# PCIE.net
KiCad netlist of a schematic drawn in Altium Designer
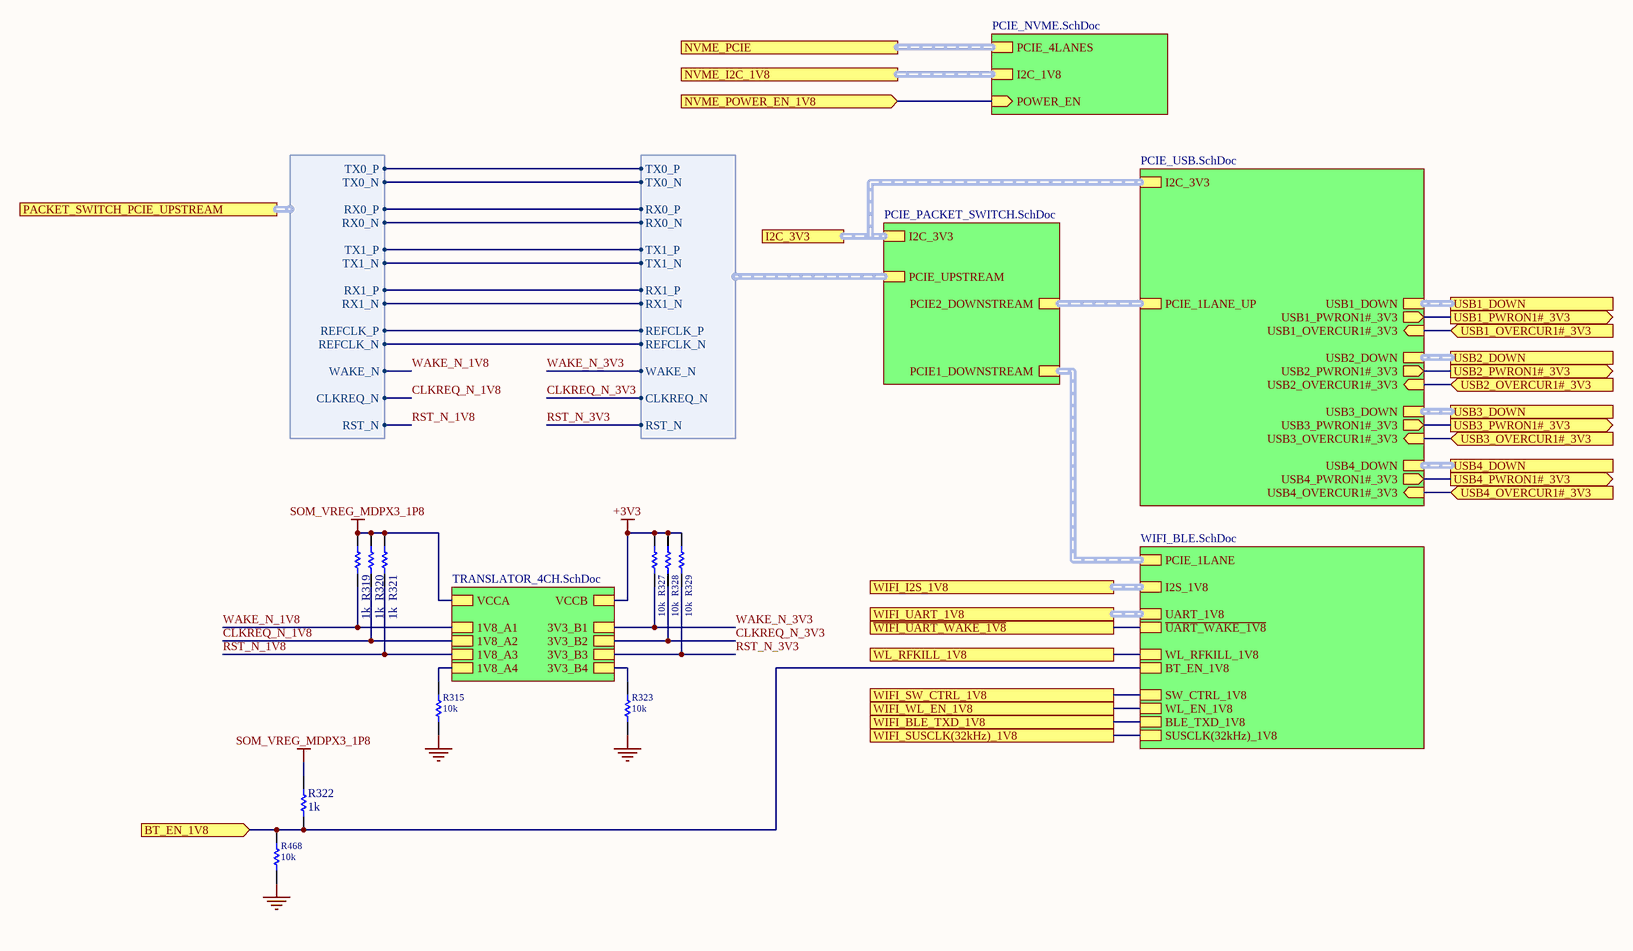
[diagram p0: PCIE.SchDoc]

(export (version "E")
  (design (tool "Eeschema 10.0.6"))
  (components
    (comp (ref "R315")
      (value "10k")
      (footprint "RES-0201")
      (description "RES CHIP 0201 10k 1% 1/20W")
      (fields (field (name "POWER") "50mW") (field (name "TOLERANCE") "1%"))
      (libsource (lib "Clean") (part "RES"))
    )
    (comp (ref "R319")
      (value "1k")
      (footprint "RES-0201")
      (description "RES CHIP 0201 1k 1% 1/20W")
      (fields (field (name "POWER") "50mW") (field (name "TOLERANCE") "1%"))
      (libsource (lib "Clean") (part "RES"))
    )
    (comp (ref "R320")
      (value "1k")
      (footprint "RES-0201")
      (description "RES CHIP 0201 1k 1% 1/20W")
      (fields (field (name "POWER") "50mW") (field (name "TOLERANCE") "1%"))
      (libsource (lib "Clean") (part "RES"))
    )
    (comp (ref "R321")
      (value "1k")
      (footprint "RES-0201")
      (description "RES CHIP 0201 1k 1% 1/20W")
      (fields (field (name "POWER") "50mW") (field (name "TOLERANCE") "1%"))
      (libsource (lib "Clean") (part "RES"))
    )
    (comp (ref "R322")
      (value "1k")
      (footprint "RES-0201")
      (description "RES CHIP 0201 1k 1% 1/20W")
      (fields (field (name "POWER") "50mW") (field (name "TOLERANCE") "1%"))
      (libsource (lib "Clean") (part "RES"))
    )
    (comp (ref "R323")
      (value "10k")
      (footprint "RES-0201")
      (description "RES CHIP 0201 10k 1% 1/20W")
      (fields (field (name "POWER") "50mW") (field (name "TOLERANCE") "1%"))
      (libsource (lib "Clean") (part "RES"))
    )
    (comp (ref "R327")
      (value "10k")
      (footprint "RES-0201")
      (description "RES CHIP 0201 10k 1% 1/20W")
      (fields (field (name "POWER") "50mW") (field (name "TOLERANCE") "1%"))
      (libsource (lib "Clean") (part "RES"))
    )
    (comp (ref "R328")
      (value "10k")
      (footprint "RES-0201")
      (description "RES CHIP 0201 10k 1% 1/20W")
      (fields (field (name "POWER") "50mW") (field (name "TOLERANCE") "1%"))
      (libsource (lib "Clean") (part "RES"))
    )
    (comp (ref "R329")
      (value "10k")
      (footprint "RES-0201")
      (description "RES CHIP 0201 10k 1% 1/20W")
      (fields (field (name "POWER") "50mW") (field (name "TOLERANCE") "1%"))
      (libsource (lib "Clean") (part "RES"))
    )
    (comp (ref "R468")
      (value "10k")
      (footprint "RES-0201")
      (description "RES CHIP 0201 10k 1% 1/20W")
      (fields (field (name "POWER") "50mW") (field (name "TOLERANCE") "1%"))
      (libsource (lib "Clean") (part "RES"))
    )
  )
  (nets
    (net (code "3") (name "+3V3") (class "Default")
      (node (ref "R327") (pin "1") (pinfunction "1_1") (pintype "passive"))
      (node (ref "R328") (pin "1") (pinfunction "1_1") (pintype "passive"))
      (node (ref "R329") (pin "1") (pinfunction "1_1") (pintype "passive"))
    )
    (net (code "4") (name "/1V8_A4") (class "Default")
      (node (ref "R315") (pin "2") (pinfunction "2_2") (pintype "passive"))
    )
    (net (code "5") (name "/3V3_B4") (class "Default")
      (node (ref "R323") (pin "2") (pinfunction "2_2") (pintype "passive"))
    )
    (net (code "6") (name "/BT_EN_1V8") (class "Default")
      (node (ref "R322") (pin "1") (pinfunction "1_1") (pintype "passive"))
      (node (ref "R468") (pin "2") (pinfunction "2_2") (pintype "passive"))
    )
    (net (code "7") (name "/CLKREQ_N_1V8") (class "Default")
      (node (ref "R320") (pin "2") (pinfunction "2_2") (pintype "passive"))
    )
    (net (code "8") (name "/CLKREQ_N_3V3") (class "Default")
      (node (ref "R328") (pin "2") (pinfunction "2_2") (pintype "passive"))
    )
    (net (code "15") (name "/RST_N_1V8") (class "Default")
      (node (ref "R321") (pin "2") (pinfunction "2_2") (pintype "passive"))
    )
    (net (code "16") (name "/RST_N_3V3") (class "Default")
      (node (ref "R329") (pin "2") (pinfunction "2_2") (pintype "passive"))
    )
    (net (code "32") (name "/WAKE_N_1V8") (class "Default")
      (node (ref "R319") (pin "2") (pinfunction "2_2") (pintype "passive"))
    )
    (net (code "33") (name "/WAKE_N_3V3") (class "Default")
      (node (ref "R327") (pin "2") (pinfunction "2_2") (pintype "passive"))
    )
    (net (code "43") (name "GND") (class "Default")
      (node (ref "R315") (pin "1") (pinfunction "1_1") (pintype "passive"))
      (node (ref "R323") (pin "1") (pinfunction "1_1") (pintype "passive"))
      (node (ref "R468") (pin "1") (pinfunction "1_1") (pintype "passive"))
    )
    (net (code "44") (name "SOM_VREG_MDPX3_1P8") (class "Default")
      (node (ref "R319") (pin "1") (pinfunction "1_1") (pintype "passive"))
      (node (ref "R320") (pin "1") (pinfunction "1_1") (pintype "passive"))
      (node (ref "R321") (pin "1") (pinfunction "1_1") (pintype "passive"))
      (node (ref "R322") (pin "2") (pinfunction "2_2") (pintype "passive"))
    )
  )
)
